# SCH_macro-pad-schematic_2024-08-08.net
KiCad netlist of a schematic drawn in EasyEDA
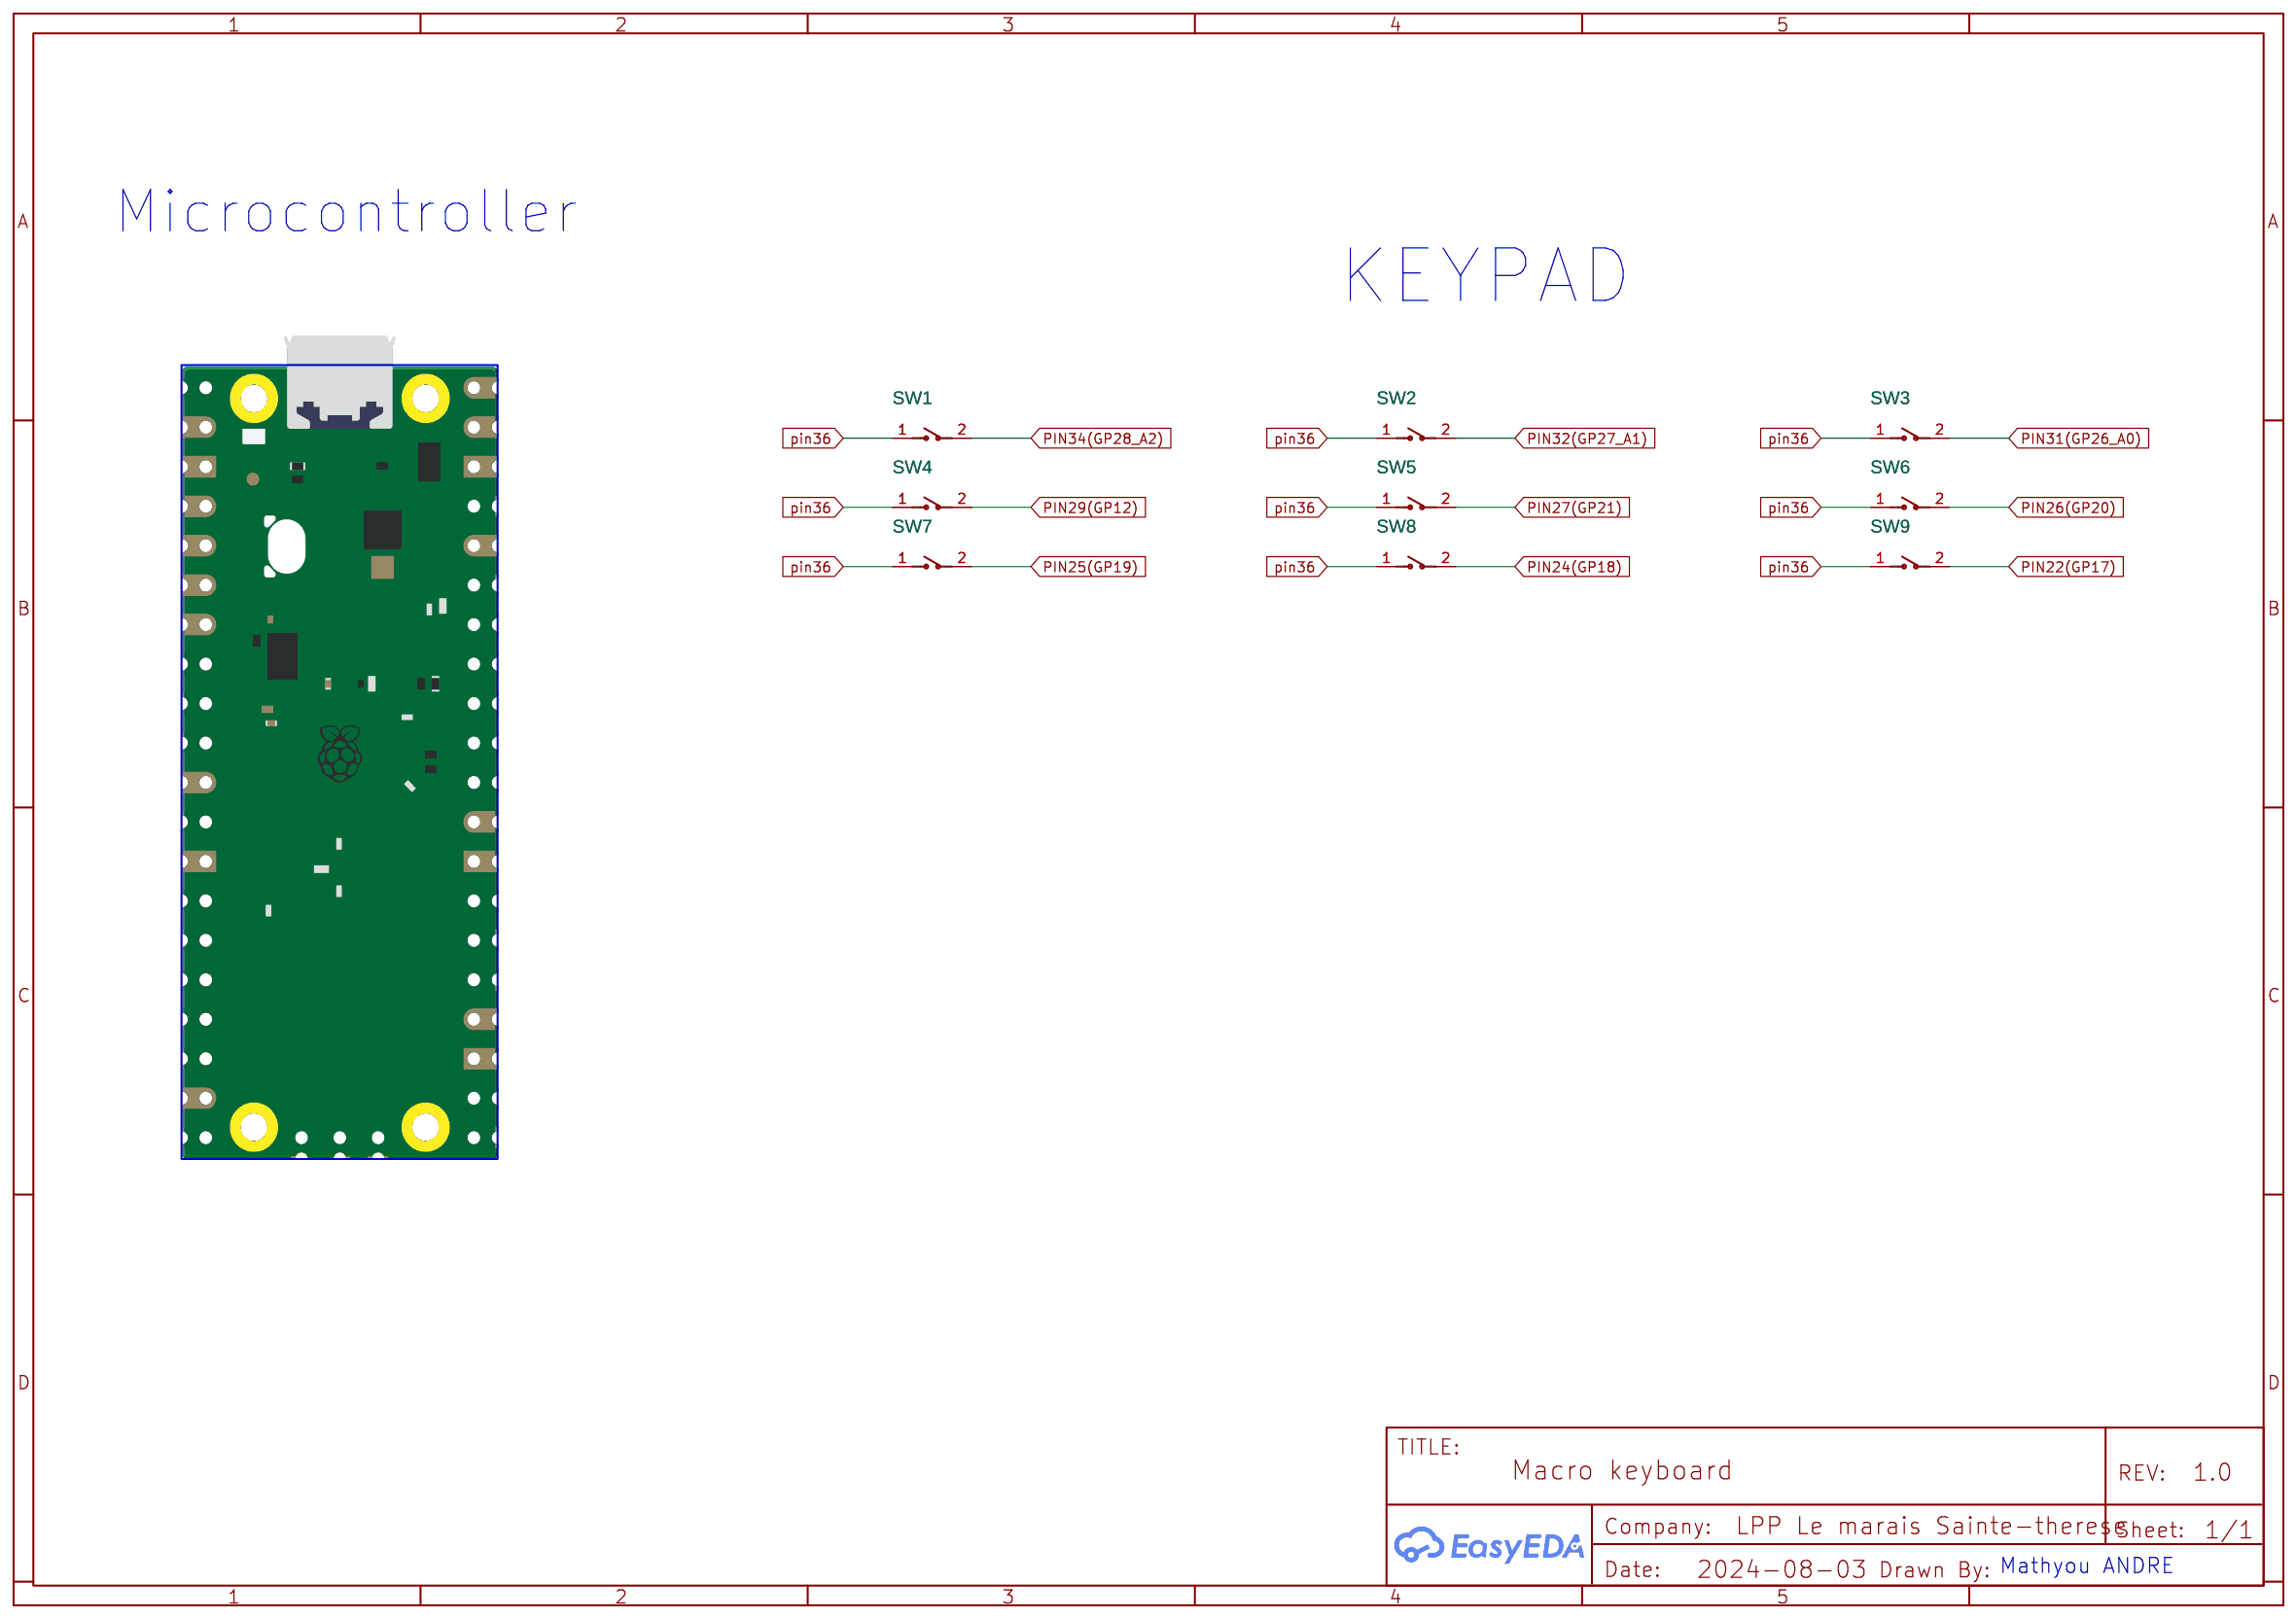
[diagram p0: schematic sheet]

(export (version "E")
  (design (tool "Eeschema 10.0.6"))
  (components
    (comp (ref "SW1")
      (value "TS-3025-B-A-B")
      (fields (field (name "Manufacturer") "XKB Connection(中国星坤)"))
      (libsource (lib "") (part "TS-3025-B-A-B"))
    )
    (comp (ref "SW2")
      (value "TS-3025-B-A-B")
      (fields (field (name "Manufacturer") "XKB Connection(中国星坤)"))
      (libsource (lib "") (part "TS-3025-B-A-B"))
    )
    (comp (ref "SW3")
      (value "TS-3025-B-A-B")
      (fields (field (name "Manufacturer") "XKB Connection(中国星坤)"))
      (libsource (lib "") (part "TS-3025-B-A-B"))
    )
    (comp (ref "SW4")
      (value "TS-3025-B-A-B")
      (fields (field (name "Manufacturer") "XKB Connection(中国星坤)"))
      (libsource (lib "") (part "TS-3025-B-A-B"))
    )
    (comp (ref "SW5")
      (value "TS-3025-B-A-B")
      (fields (field (name "Manufacturer") "XKB Connection(中国星坤)"))
      (libsource (lib "") (part "TS-3025-B-A-B"))
    )
    (comp (ref "SW6")
      (value "TS-3025-B-A-B")
      (fields (field (name "Manufacturer") "XKB Connection(中国星坤)"))
      (libsource (lib "") (part "TS-3025-B-A-B"))
    )
    (comp (ref "SW7")
      (value "TS-3025-B-A-B")
      (fields (field (name "Manufacturer") "XKB Connection(中国星坤)"))
      (libsource (lib "") (part "TS-3025-B-A-B"))
    )
    (comp (ref "SW8")
      (value "TS-3025-B-A-B")
      (fields (field (name "Manufacturer") "XKB Connection(中国星坤)"))
      (libsource (lib "") (part "TS-3025-B-A-B"))
    )
    (comp (ref "SW9")
      (value "TS-3025-B-A-B")
      (fields (field (name "Manufacturer") "XKB Connection(中国星坤)"))
      (libsource (lib "") (part "TS-3025-B-A-B"))
    )
  )
  (nets
    (net (code "1") (name "PIN22(GP17)") (class "Default")
      (node (ref "SW9") (pin "2") (pinfunction "2_2") (pintype "unspecified"))
    )
    (net (code "2") (name "PIN24(GP18)") (class "Default")
      (node (ref "SW8") (pin "2") (pinfunction "2_2") (pintype "unspecified"))
    )
    (net (code "3") (name "PIN25(GP19)") (class "Default")
      (node (ref "SW7") (pin "2") (pinfunction "2_2") (pintype "unspecified"))
    )
    (net (code "4") (name "PIN26(GP20)") (class "Default")
      (node (ref "SW6") (pin "2") (pinfunction "2_2") (pintype "unspecified"))
    )
    (net (code "5") (name "PIN27(GP21)") (class "Default")
      (node (ref "SW5") (pin "2") (pinfunction "2_2") (pintype "unspecified"))
    )
    (net (code "6") (name "PIN29(GP12)") (class "Default")
      (node (ref "SW4") (pin "2") (pinfunction "2_2") (pintype "unspecified"))
    )
    (net (code "7") (name "PIN31(GP26_A0)") (class "Default")
      (node (ref "SW3") (pin "2") (pinfunction "2_2") (pintype "unspecified"))
    )
    (net (code "8") (name "PIN32(GP27_A1)") (class "Default")
      (node (ref "SW2") (pin "2") (pinfunction "2_2") (pintype "unspecified"))
    )
    (net (code "9") (name "PIN34(GP28_A2)") (class "Default")
      (node (ref "SW1") (pin "2") (pinfunction "2_2") (pintype "unspecified"))
    )
    (net (code "10") (name "pin36") (class "Default")
      (node (ref "SW1") (pin "1") (pinfunction "1_1") (pintype "unspecified"))
      (node (ref "SW2") (pin "1") (pinfunction "1_1") (pintype "unspecified"))
      (node (ref "SW3") (pin "1") (pinfunction "1_1") (pintype "unspecified"))
      (node (ref "SW4") (pin "1") (pinfunction "1_1") (pintype "unspecified"))
      (node (ref "SW5") (pin "1") (pinfunction "1_1") (pintype "unspecified"))
      (node (ref "SW6") (pin "1") (pinfunction "1_1") (pintype "unspecified"))
      (node (ref "SW7") (pin "1") (pinfunction "1_1") (pintype "unspecified"))
      (node (ref "SW8") (pin "1") (pinfunction "1_1") (pintype "unspecified"))
      (node (ref "SW9") (pin "1") (pinfunction "1_1") (pintype "unspecified"))
    )
  )
)
